# MAIN.net
KiCad netlist of a schematic drawn in Altium Designer
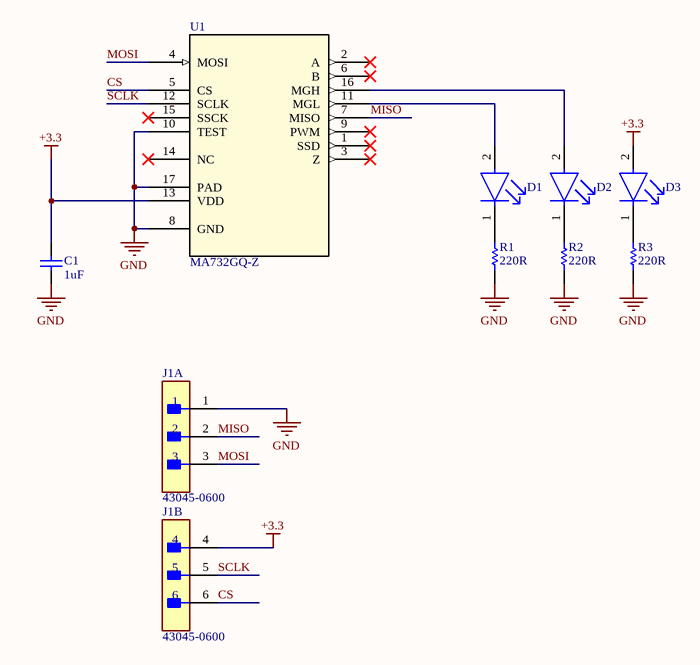
[diagram p0: MAIN.SchDoc]

(export (version "E")
  (design (tool "Eeschema 10.0.6"))
  (components
    (comp (ref "C1")
      (value "1uF")
      (footprint "CAPC2013X145X50LL20T25")
      (fields (field (name "MANUFACTURER") "Kemet") (field (name "PART NUMBER") "C0805C105K4PACTU"))
      (libsource (lib "Altium Content Vault") (part "CAP"))
    )
    (comp (ref "D1")
      (value "150080SS75000")
      (footprint "FP-150080SS75000-MFG")
      (description "LED RED CLEAR 0805 SMD")
      (libsource (lib "Altium Content Vault") (part "8706943c75ba83719d021d2fdc84c58"))
    )
    (comp (ref "D2")
      (value "150080SS75000")
      (footprint "FP-150080SS75000-MFG")
      (description "LED RED CLEAR 0805 SMD")
      (libsource (lib "Altium Content Vault") (part "8706943c75ba83719d021d2fdc84c58"))
    )
    (comp (ref "D3")
      (value "150080SS75000")
      (footprint "FP-150080SS75000-MFG")
      (description "LED RED CLEAR 0805 SMD")
      (libsource (lib "Altium Content Vault") (part "8706943c75ba83719d021d2fdc84c58"))
    )
    (comp (ref "J1")
      (value "43045-0600")
      (footprint "FP-0430450600-MFG")
      (description "43045-0600 Connector Wire to Board Header 6 Position 3mm Solder Right Angle Thru-Hole Tray")
      (libsource (lib "Altium Content Vault") (part "7bb5f7ddfb2bec276e641070710345c"))
    )
    (comp (ref "R1")
      (value "220R")
      (footprint "RESC2013X70X40NL20T20")
      (description "Chip Resistor, 4.7 KOhm, +/- 1%, 0.125 W, -55 to 155 degC, 0805 (2012 Metric), RoHS, Tape and Reel")
      (fields (field (name "MANUFACTURER") "Panasonic"))
      (libsource (lib "Altium Content Vault") (part "RES-2"))
    )
    (comp (ref "R2")
      (value "220R")
      (footprint "RESC2013X70X40NL20T20")
      (description "Chip Resistor, 4.7 KOhm, +/- 1%, 0.125 W, -55 to 155 degC, 0805 (2012 Metric), RoHS, Tape and Reel")
      (fields (field (name "MANUFACTURER") "Panasonic"))
      (libsource (lib "Altium Content Vault") (part "RES-2"))
    )
    (comp (ref "R3")
      (value "220R")
      (footprint "RESC2013X70X40NL20T20")
      (description "Chip Resistor, 4.7 KOhm, +/- 1%, 0.125 W, -55 to 155 degC, 0805 (2012 Metric), RoHS, Tape and Reel")
      (fields (field (name "MANUFACTURER") "Panasonic"))
      (libsource (lib "Altium Content Vault") (part "RES-2"))
    )
    (comp (ref "U1")
      (value "MA732GQ-Z")
      (footprint "QFN-16_MA732")
      (description "No Description Available")
      (fields (field (name "COPYRIGHT") "Copyright (C) 2023 Ultra Librarian. All rights reserved."))
      (libsource (lib "MA732GQ-Z") (part "MA732GQ-Z"))
    )
  )
  (nets
    (net (code "1") (name "+3.3") (class "Default")
      (node (ref "C1") (pin "2") (pinfunction "2_2") (pintype "passive"))
      (node (ref "D3") (pin "2") (pinfunction "A_2") (pintype "passive"))
      (node (ref "J1") (pin "4") (pinfunction "4_4") (pintype "passive"))
      (node (ref "U1") (pin "13") (pinfunction "VDD_13") (pintype "power_in"))
    )
    (net (code "2") (name "/CS") (class "Default")
      (node (ref "J1") (pin "6") (pinfunction "6_6") (pintype "passive"))
      (node (ref "U1") (pin "5") (pinfunction "CS_5") (pintype "passive"))
    )
    (net (code "3") (name "/MISO") (class "Default")
      (node (ref "J1") (pin "2") (pinfunction "2_2") (pintype "passive"))
      (node (ref "U1") (pin "7") (pinfunction "MISO_7") (pintype "output"))
    )
    (net (code "4") (name "/MOSI") (class "Default")
      (node (ref "J1") (pin "3") (pinfunction "3_3") (pintype "passive"))
      (node (ref "U1") (pin "4") (pinfunction "MOSI_4") (pintype "input"))
    )
    (net (code "5") (name "/SCLK") (class "Default")
      (node (ref "J1") (pin "5") (pinfunction "5_5") (pintype "passive"))
      (node (ref "U1") (pin "12") (pinfunction "SCLK_12") (pintype "passive"))
    )
    (net (code "6") (name "GND") (class "Default")
      (node (ref "C1") (pin "1") (pinfunction "1_1") (pintype "passive"))
      (node (ref "J1") (pin "1") (pinfunction "1_1") (pintype "passive"))
      (node (ref "R1") (pin "1") (pinfunction "1_1") (pintype "passive"))
      (node (ref "R2") (pin "1") (pinfunction "1_1") (pintype "passive"))
      (node (ref "R3") (pin "1") (pinfunction "1_1") (pintype "passive"))
      (node (ref "U1") (pin "10") (pinfunction "TEST_10") (pintype "passive"))
      (node (ref "U1") (pin "17") (pinfunction "PAD_17") (pintype "power_in"))
      (node (ref "U1") (pin "8") (pinfunction "GND_8") (pintype "power_in"))
    )
    (net (code "7") (name "Net-(D1-A)") (class "Default")
      (node (ref "D1") (pin "2") (pinfunction "A_2") (pintype "passive"))
      (node (ref "U1") (pin "11") (pinfunction "MGL_11") (pintype "output"))
    )
    (net (code "8") (name "Net-(D1-C)") (class "Default")
      (node (ref "D1") (pin "1") (pinfunction "C_1") (pintype "passive"))
      (node (ref "R1") (pin "2") (pinfunction "2_2") (pintype "passive"))
    )
    (net (code "9") (name "Net-(D2-A)") (class "Default")
      (node (ref "D2") (pin "2") (pinfunction "A_2") (pintype "passive"))
      (node (ref "U1") (pin "16") (pinfunction "MGH_16") (pintype "output"))
    )
    (net (code "10") (name "Net-(D2-C)") (class "Default")
      (node (ref "D2") (pin "1") (pinfunction "C_1") (pintype "passive"))
      (node (ref "R2") (pin "2") (pinfunction "2_2") (pintype "passive"))
    )
    (net (code "11") (name "Net-(D3-C)") (class "Default")
      (node (ref "D3") (pin "1") (pinfunction "C_1") (pintype "passive"))
      (node (ref "R3") (pin "2") (pinfunction "2_2") (pintype "passive"))
    )
    (net (code "12") (name "unconnected-(U1-A-Pad2)") (class "Default")
      (node (ref "U1") (pin "2") (pinfunction "A_2") (pintype "output+no_connect"))
    )
    (net (code "13") (name "unconnected-(U1-B-Pad6)") (class "Default")
      (node (ref "U1") (pin "6") (pinfunction "B_6") (pintype "output+no_connect"))
    )
    (net (code "14") (name "unconnected-(U1-NC-Pad14)") (class "Default")
      (node (ref "U1") (pin "14") (pinfunction "NC_14") (pintype "passive+no_connect"))
    )
    (net (code "15") (name "unconnected-(U1-PWM-Pad9)") (class "Default")
      (node (ref "U1") (pin "9") (pinfunction "PWM_9") (pintype "output+no_connect"))
    )
    (net (code "16") (name "unconnected-(U1-SSCK-Pad15)") (class "Default")
      (node (ref "U1") (pin "15") (pinfunction "SSCK_15") (pintype "passive+no_connect"))
    )
    (net (code "17") (name "unconnected-(U1-SSD-Pad1)") (class "Default")
      (node (ref "U1") (pin "1") (pinfunction "SSD_1") (pintype "output+no_connect"))
    )
    (net (code "18") (name "unconnected-(U1-Z-Pad3)") (class "Default")
      (node (ref "U1") (pin "3") (pinfunction "Z_3") (pintype "output+no_connect"))
    )
  )
)
